# RS485.net
KiCad netlist of a schematic drawn in Altium Designer
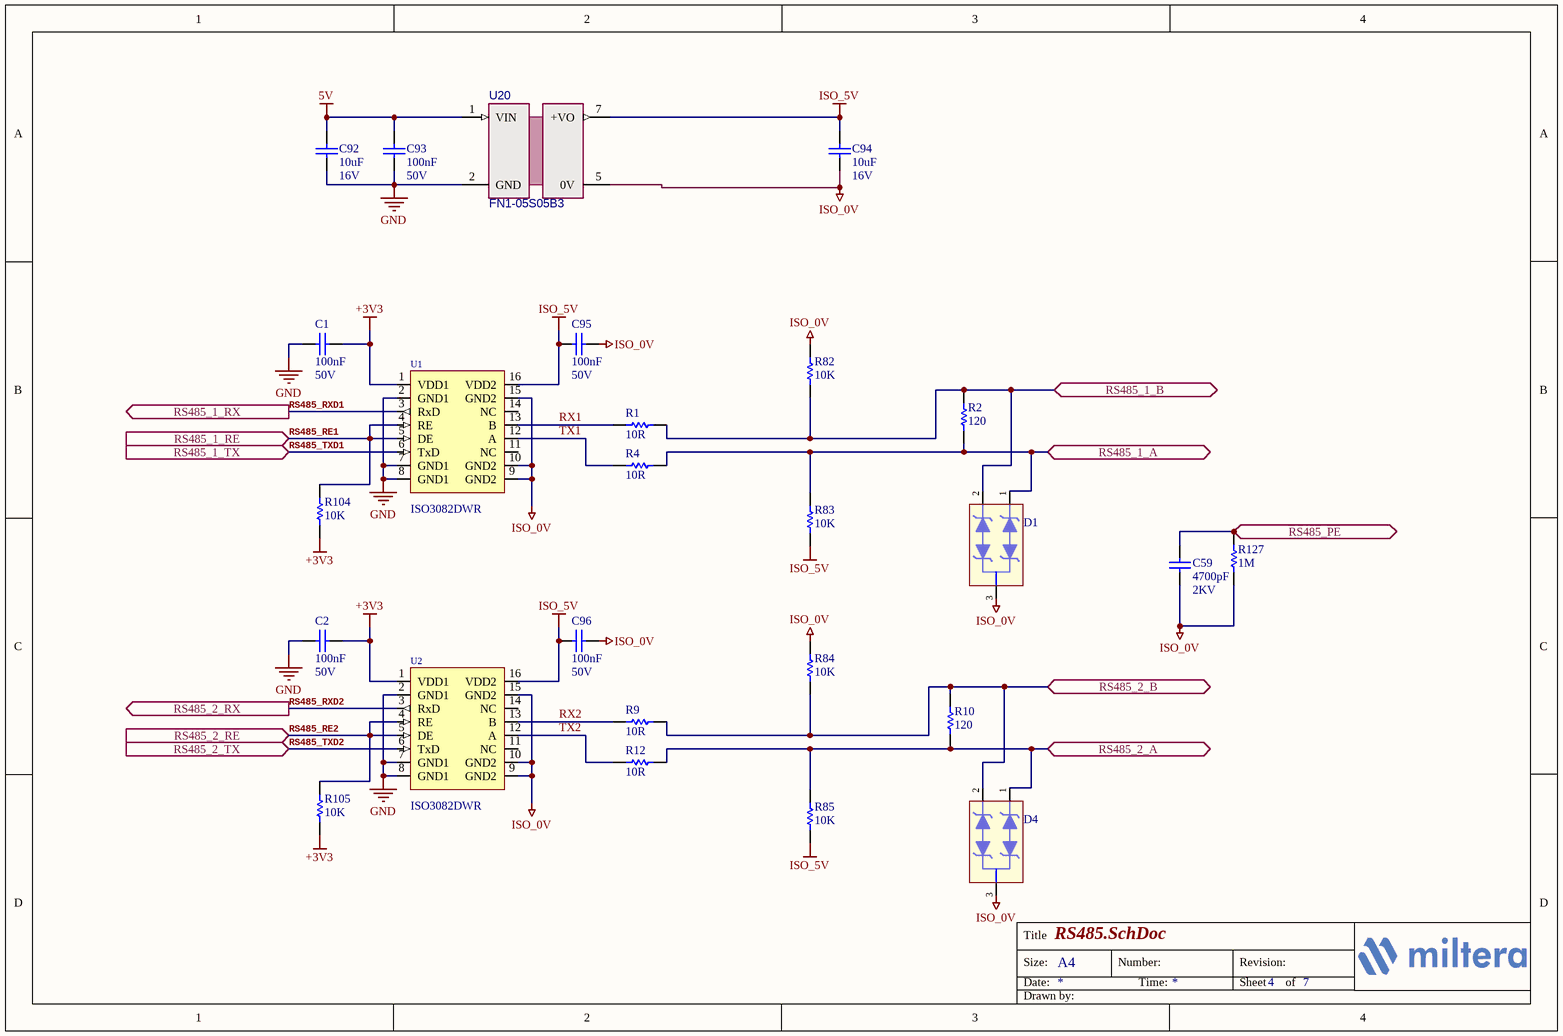
[diagram p0: RS485.SchDoc]

(export (version "E")
  (design (tool "Eeschema 10.0.6"))
  (components
    (comp (ref "C1")
      (value "100nF")
      (footprint "CAP_0603")
      (description "CAP CER 100nF 50VDC %10 X7R SMD")
      (fields
        (field (name "VOLTAGE") "50V")
        (field (name "MANUFACTURER") "Samsung")
        (field (name "MANUFACTURER PART NUMBER") "CL10B104KB8NNNL")
      )
      (libsource (lib "open-components") (part "CAP"))
    )
    (comp (ref "C2")
      (value "100nF")
      (footprint "CAP_0603")
      (description "CAP CER 100nF 50VDC %10 X7R SMD")
      (fields
        (field (name "VOLTAGE") "50V")
        (field (name "MANUFACTURER") "Samsung")
        (field (name "MANUFACTURER PART NUMBER") "CL10B104KB8NNNL")
      )
      (libsource (lib "open-components") (part "CAP"))
    )
    (comp (ref "C59")
      (value "4700pF")
      (footprint "CAPC4632X300N")
      (description "CAP CER 4.7nF 2kV X7R 1812")
      (fields
        (field (name "VOLTAGE") "2KV")
        (field (name "MANUFACTURER") "Johanson Dielectrics")
        (field (name "MANUFACTURER PART NUMBER") "202S43W472KV4E")
      )
      (libsource (lib "open-components") (part "CAP"))
    )
    (comp (ref "C92")
      (value "10uF")
      (footprint "CAP_0805")
      (description "CAP CER 10UF 16VDC %10 X5R SMD")
      (fields
        (field (name "VOLTAGE") "16V")
        (field (name "MANUFACTURER") "Samsung")
        (field (name "MANUFACTURER PART NUMBER") "CL21A106KOQNNNE")
      )
      (libsource (lib "open-components") (part "CAP"))
    )
    (comp (ref "C93")
      (value "100nF")
      (footprint "CAP_0603")
      (description "CAP CER 100nF 50VDC %10 X7R SMD")
      (fields
        (field (name "VOLTAGE") "50V")
        (field (name "MANUFACTURER") "Samsung")
        (field (name "MANUFACTURER PART NUMBER") "CL10B104KB8NNNL")
      )
      (libsource (lib "open-components") (part "CAP"))
    )
    (comp (ref "C94")
      (value "10uF")
      (footprint "CAP_0805")
      (description "CAP CER 10UF 16VDC %10 X5R SMD")
      (fields
        (field (name "VOLTAGE") "16V")
        (field (name "MANUFACTURER") "Samsung")
        (field (name "MANUFACTURER PART NUMBER") "CL21A106KOQNNNE")
      )
      (libsource (lib "open-components") (part "CAP"))
    )
    (comp (ref "C95")
      (value "100nF")
      (footprint "CAP_0603")
      (description "CAP CER 100nF 50VDC %10 X7R SMD")
      (fields
        (field (name "VOLTAGE") "50V")
        (field (name "MANUFACTURER") "Samsung")
        (field (name "MANUFACTURER PART NUMBER") "CL10B104KB8NNNL")
      )
      (libsource (lib "open-components") (part "CAP"))
    )
    (comp (ref "C96")
      (value "100nF")
      (footprint "CAP_0603")
      (description "CAP CER 100nF 50VDC %10 X7R SMD")
      (fields
        (field (name "VOLTAGE") "50V")
        (field (name "MANUFACTURER") "Samsung")
        (field (name "MANUFACTURER PART NUMBER") "CL10B104KB8NNNL")
      )
      (libsource (lib "open-components") (part "CAP"))
    )
    (comp (ref "D1")
      (value "TVS-RS485")
      (footprint "SOT-23")
      (description "TVS DIODE 7V/12V 14V/26V SOT23-3")
      (fields
        (field (name "MANUFACTURER PART NUMBER") "SM712-02HTG")
        (field (name "MANUFACTURER") "LittelFuse Inc.")
      )
      (libsource (lib "open-components") (part "TVS-RS485"))
    )
    (comp (ref "D4")
      (value "TVS-RS485")
      (footprint "SOT-23")
      (description "TVS DIODE 7V/12V 14V/26V SOT23-3")
      (fields
        (field (name "MANUFACTURER PART NUMBER") "SM712-02HTG")
        (field (name "MANUFACTURER") "LittelFuse Inc.")
      )
      (libsource (lib "open-components") (part "TVS-RS485"))
    )
    (comp (ref "R1")
      (value "10R")
      (footprint "RES_0603")
      (description "RES 0603 10 Ohms 1% 1/10W-S 100PPM")
      (fields
        (field (name "MANUFACTURER") "ROYALOHM")
        (field (name "MANUFACTURER PART NUMBER") "0603SAF100JT5E")
      )
      (libsource (lib "open-components") (part "RES"))
    )
    (comp (ref "R2")
      (value "120")
      (footprint "RES_0603")
      (description "RES SMD 120 OHM 1% 1/10W 0603")
      (fields
        (field (name "MANUFACTURER") "Yageo")
        (field (name "MANUFACTURER PART NUMBER") "RC0603FR-07120RL")
      )
      (libsource (lib "open-components") (part "RES"))
    )
    (comp (ref "R4")
      (value "10R")
      (footprint "RES_0603")
      (description "RES 0603 10 Ohms 1% 1/10W-S 100PPM")
      (fields
        (field (name "MANUFACTURER") "ROYALOHM")
        (field (name "MANUFACTURER PART NUMBER") "0603SAF100JT5E")
      )
      (libsource (lib "open-components") (part "RES"))
    )
    (comp (ref "R9")
      (value "10R")
      (footprint "RES_0603")
      (description "RES 0603 10 Ohms 1% 1/10W-S 100PPM")
      (fields
        (field (name "MANUFACTURER") "ROYALOHM")
        (field (name "MANUFACTURER PART NUMBER") "0603SAF100JT5E")
      )
      (libsource (lib "open-components") (part "RES"))
    )
    (comp (ref "R10")
      (value "120")
      (footprint "RES_0603")
      (description "RES SMD 120 OHM 1% 1/10W 0603")
      (fields
        (field (name "MANUFACTURER") "Yageo")
        (field (name "MANUFACTURER PART NUMBER") "RC0603FR-07120RL")
      )
      (libsource (lib "open-components") (part "RES"))
    )
    (comp (ref "R12")
      (value "10R")
      (footprint "RES_0603")
      (description "RES 0603 10 Ohms 1% 1/10W-S 100PPM")
      (fields
        (field (name "MANUFACTURER") "ROYALOHM")
        (field (name "MANUFACTURER PART NUMBER") "0603SAF100JT5E")
      )
      (libsource (lib "open-components") (part "RES"))
    )
    (comp (ref "R82")
      (value "10K")
      (footprint "RES_0603")
      (description "RES 0603 10k Ohms %1 1/10W 100PPM")
      (fields
        (field (name "MANUFACTURER") "ROYALOHM")
        (field (name "MANUFACTURER PART NUMBER") "0603SAF1002T5E")
      )
      (libsource (lib "open-components") (part "RES"))
    )
    (comp (ref "R83")
      (value "10K")
      (footprint "RES_0603")
      (description "RES 0603 10k Ohms %1 1/10W 100PPM")
      (fields
        (field (name "MANUFACTURER") "ROYALOHM")
        (field (name "MANUFACTURER PART NUMBER") "0603SAF1002T5E")
      )
      (libsource (lib "open-components") (part "RES"))
    )
    (comp (ref "R84")
      (value "10K")
      (footprint "RES_0603")
      (description "RES 0603 10k Ohms %1 1/10W 100PPM")
      (fields
        (field (name "MANUFACTURER") "ROYALOHM")
        (field (name "MANUFACTURER PART NUMBER") "0603SAF1002T5E")
      )
      (libsource (lib "open-components") (part "RES"))
    )
    (comp (ref "R85")
      (value "10K")
      (footprint "RES_0603")
      (description "RES 0603 10k Ohms %1 1/10W 100PPM")
      (fields
        (field (name "MANUFACTURER") "ROYALOHM")
        (field (name "MANUFACTURER PART NUMBER") "0603SAF1002T5E")
      )
      (libsource (lib "open-components") (part "RES"))
    )
    (comp (ref "R104")
      (value "10K")
      (footprint "RES_0603")
      (description "RES 0603 10k Ohms %1 1/10W 100PPM")
      (fields
        (field (name "MANUFACTURER") "ROYALOHM")
        (field (name "MANUFACTURER PART NUMBER") "0603SAF1002T5E")
      )
      (libsource (lib "open-components") (part "RES"))
    )
    (comp (ref "R105")
      (value "10K")
      (footprint "RES_0603")
      (description "RES 0603 10k Ohms %1 1/10W 100PPM")
      (fields
        (field (name "MANUFACTURER") "ROYALOHM")
        (field (name "MANUFACTURER PART NUMBER") "0603SAF1002T5E")
      )
      (libsource (lib "open-components") (part "RES"))
    )
    (comp (ref "R127")
      (value "1M")
      (footprint "RES_1206")
      (description "RES 1MΩ ±1% 300mW 1206")
      (fields
        (field (name "MANUFACTURER") "VISHAY")
        (field (name "MANUFACTURER PART NUMBER") "CRMA1206AF1M00FKEF")
      )
      (libsource (lib "open-components") (part "RES"))
    )
    (comp (ref "U1")
      (value "ISO3082DWR")
      (footprint "16-SOIC")
      (fields
        (field (name "MANUFACTURER PART NUMBER") "ISO3082DWR")
        (field (name "MANUFACTURER") "Texas Ins.")
      )
      (libsource (lib "open-components") (part "ISO3082DWR"))
    )
    (comp (ref "U2")
      (value "ISO3082DWR")
      (footprint "16-SOIC")
      (fields
        (field (name "MANUFACTURER PART NUMBER") "ISO3082DWR")
        (field (name "MANUFACTURER") "Texas Ins.")
      )
      (libsource (lib "open-components") (part "ISO3082DWR"))
    )
    (comp (ref "U20")
      (value "FN1-05S05B3")
      (footprint "F0505S1WR3")
      (description "Isolated Module DC DC Converter 1 Output 5V 200mA 4.5V - 5.5V Input")
      (fields (field (name "MANUFACTURER") "AIPU"))
      (libsource (lib "Schlib1") (part "F0505S-1WR3_FN1-05S05B3"))
    )
  )
  (nets
    (net (code "1") (name "+3V3") (class "Default")
      (node (ref "C1") (pin "2") (pinfunction "2_2") (pintype "passive"))
      (node (ref "C2") (pin "2") (pinfunction "2_2") (pintype "passive"))
      (node (ref "R104") (pin "2") (pinfunction "2_2") (pintype "passive"))
      (node (ref "R105") (pin "2") (pinfunction "2_2") (pintype "passive"))
      (node (ref "U1") (pin "1") (pinfunction "VDD1_1") (pintype "power_in"))
      (node (ref "U2") (pin "1") (pinfunction "VDD1_1") (pintype "power_in"))
    )
    (net (code "2") (name "/RS485_1_A") (class "Default")
      (node (ref "D1") (pin "1") (pinfunction "1_1") (pintype "passive"))
      (node (ref "R2") (pin "2") (pinfunction "2_2") (pintype "passive"))
      (node (ref "R4") (pin "2") (pinfunction "2_2") (pintype "passive"))
      (node (ref "R83") (pin "1") (pinfunction "1_1") (pintype "passive"))
    )
    (net (code "3") (name "/RS485_1_B") (class "Default")
      (node (ref "D1") (pin "2") (pinfunction "2_2") (pintype "passive"))
      (node (ref "R1") (pin "2") (pinfunction "2_2") (pintype "passive"))
      (node (ref "R2") (pin "1") (pinfunction "1_1") (pintype "passive"))
      (node (ref "R82") (pin "2") (pinfunction "2_2") (pintype "passive"))
    )
    (net (code "4") (name "/RS485_2_A") (class "Default")
      (node (ref "D4") (pin "1") (pinfunction "1_1") (pintype "passive"))
      (node (ref "R10") (pin "2") (pinfunction "2_2") (pintype "passive"))
      (node (ref "R12") (pin "2") (pinfunction "2_2") (pintype "passive"))
      (node (ref "R85") (pin "1") (pinfunction "1_1") (pintype "passive"))
    )
    (net (code "5") (name "/RS485_2_B") (class "Default")
      (node (ref "D4") (pin "2") (pinfunction "2_2") (pintype "passive"))
      (node (ref "R10") (pin "1") (pinfunction "1_1") (pintype "passive"))
      (node (ref "R84") (pin "2") (pinfunction "2_2") (pintype "passive"))
      (node (ref "R9") (pin "2") (pinfunction "2_2") (pintype "passive"))
    )
    (net (code "6") (name "/RS485_PE") (class "Default")
      (node (ref "C59") (pin "2") (pinfunction "2_2") (pintype "passive"))
      (node (ref "R127") (pin "1") (pinfunction "1_1") (pintype "passive"))
    )
    (net (code "7") (name "/RS485_RE1") (class "Default")
      (node (ref "R104") (pin "1") (pinfunction "1_1") (pintype "passive"))
      (node (ref "U1") (pin "4") (pinfunction "RE_4") (pintype "input"))
      (node (ref "U1") (pin "5") (pinfunction "DE_5") (pintype "input"))
    )
    (net (code "8") (name "/RS485_RE2") (class "Default")
      (node (ref "R105") (pin "1") (pinfunction "1_1") (pintype "passive"))
      (node (ref "U2") (pin "4") (pinfunction "RE_4") (pintype "input"))
      (node (ref "U2") (pin "5") (pinfunction "DE_5") (pintype "input"))
    )
    (net (code "9") (name "/RS485_RXD1") (class "Default")
      (node (ref "U1") (pin "3") (pinfunction "RxD_3") (pintype "output"))
    )
    (net (code "10") (name "/RS485_RXD2") (class "Default")
      (node (ref "U2") (pin "3") (pinfunction "RxD_3") (pintype "output"))
    )
    (net (code "11") (name "/RS485_TXD1") (class "Default")
      (node (ref "U1") (pin "6") (pinfunction "TxD_6") (pintype "input"))
    )
    (net (code "12") (name "/RS485_TXD2") (class "Default")
      (node (ref "U2") (pin "6") (pinfunction "TxD_6") (pintype "input"))
    )
    (net (code "13") (name "/RX1") (class "Default")
      (node (ref "R1") (pin "1") (pinfunction "1_1") (pintype "passive"))
      (node (ref "U1") (pin "13") (pinfunction "B_13") (pintype "bidirectional"))
    )
    (net (code "14") (name "/RX2") (class "Default")
      (node (ref "R9") (pin "1") (pinfunction "1_1") (pintype "passive"))
      (node (ref "U2") (pin "13") (pinfunction "B_13") (pintype "bidirectional"))
    )
    (net (code "15") (name "/TX1") (class "Default")
      (node (ref "R4") (pin "1") (pinfunction "1_1") (pintype "passive"))
      (node (ref "U1") (pin "12") (pinfunction "A_12") (pintype "bidirectional"))
    )
    (net (code "16") (name "/TX2") (class "Default")
      (node (ref "R12") (pin "1") (pinfunction "1_1") (pintype "passive"))
      (node (ref "U2") (pin "12") (pinfunction "A_12") (pintype "bidirectional"))
    )
    (net (code "17") (name "5V") (class "Default")
      (node (ref "C92") (pin "1") (pinfunction "1_1") (pintype "passive"))
      (node (ref "C93") (pin "1") (pinfunction "1_1") (pintype "passive"))
      (node (ref "U20") (pin "1") (pinfunction "VIN_1") (pintype "input"))
    )
    (net (code "18") (name "GND") (class "Default")
      (node (ref "C1") (pin "1") (pinfunction "1_1") (pintype "passive"))
      (node (ref "C2") (pin "1") (pinfunction "1_1") (pintype "passive"))
      (node (ref "C92") (pin "2") (pinfunction "2_2") (pintype "passive"))
      (node (ref "C93") (pin "2") (pinfunction "2_2") (pintype "passive"))
      (node (ref "U1") (pin "2") (pinfunction "GND1_2") (pintype "bidirectional"))
      (node (ref "U1") (pin "7") (pinfunction "GND1_7") (pintype "bidirectional"))
      (node (ref "U1") (pin "8") (pinfunction "GND1_8") (pintype "bidirectional"))
      (node (ref "U2") (pin "2") (pinfunction "GND1_2") (pintype "bidirectional"))
      (node (ref "U2") (pin "7") (pinfunction "GND1_7") (pintype "bidirectional"))
      (node (ref "U2") (pin "8") (pinfunction "GND1_8") (pintype "bidirectional"))
      (node (ref "U20") (pin "2") (pinfunction "GND_2") (pintype "power_in"))
    )
    (net (code "19") (name "ISO_0V") (class "Default")
      (node (ref "C59") (pin "1") (pinfunction "1_1") (pintype "passive"))
      (node (ref "C94") (pin "2") (pinfunction "2_2") (pintype "passive"))
      (node (ref "C95") (pin "2") (pinfunction "2_2") (pintype "passive"))
      (node (ref "C96") (pin "2") (pinfunction "2_2") (pintype "passive"))
      (node (ref "D1") (pin "3") (pinfunction "3_3") (pintype "passive"))
      (node (ref "D4") (pin "3") (pinfunction "3_3") (pintype "passive"))
      (node (ref "R127") (pin "2") (pinfunction "2_2") (pintype "passive"))
      (node (ref "R82") (pin "1") (pinfunction "1_1") (pintype "passive"))
      (node (ref "R84") (pin "1") (pinfunction "1_1") (pintype "passive"))
      (node (ref "U1") (pin "10") (pinfunction "GND2_10") (pintype "bidirectional"))
      (node (ref "U1") (pin "15") (pinfunction "GND2_15") (pintype "bidirectional"))
      (node (ref "U1") (pin "9") (pinfunction "GND2_9") (pintype "bidirectional"))
      (node (ref "U2") (pin "10") (pinfunction "GND2_10") (pintype "bidirectional"))
      (node (ref "U2") (pin "15") (pinfunction "GND2_15") (pintype "bidirectional"))
      (node (ref "U2") (pin "9") (pinfunction "GND2_9") (pintype "bidirectional"))
      (node (ref "U20") (pin "5") (pinfunction "0V_5") (pintype "passive"))
    )
    (net (code "20") (name "ISO_5V") (class "Default")
      (node (ref "C94") (pin "1") (pinfunction "1_1") (pintype "passive"))
      (node (ref "C95") (pin "1") (pinfunction "1_1") (pintype "passive"))
      (node (ref "C96") (pin "1") (pinfunction "1_1") (pintype "passive"))
      (node (ref "R83") (pin "2") (pinfunction "2_2") (pintype "passive"))
      (node (ref "R85") (pin "2") (pinfunction "2_2") (pintype "passive"))
      (node (ref "U1") (pin "16") (pinfunction "VDD2_16") (pintype "power_in"))
      (node (ref "U2") (pin "16") (pinfunction "VDD2_16") (pintype "power_in"))
      (node (ref "U20") (pin "7") (pinfunction "+VO_7") (pintype "output"))
    )
    (net (code "21") (name "unconnected-(U1-NC-Pad11)") (class "Default")
      (node (ref "U1") (pin "11") (pinfunction "NC_11") (pintype "bidirectional"))
    )
    (net (code "22") (name "unconnected-(U1-NC-Pad14)") (class "Default")
      (node (ref "U1") (pin "14") (pinfunction "NC_14") (pintype "bidirectional"))
    )
    (net (code "23") (name "unconnected-(U2-NC-Pad11)") (class "Default")
      (node (ref "U2") (pin "11") (pinfunction "NC_11") (pintype "bidirectional"))
    )
    (net (code "24") (name "unconnected-(U2-NC-Pad14)") (class "Default")
      (node (ref "U2") (pin "14") (pinfunction "NC_14") (pintype "bidirectional"))
    )
  )
)
